# MIC2250-1YD5-TR_breakout.net
KiCad netlist of a schematic drawn in EAGLE
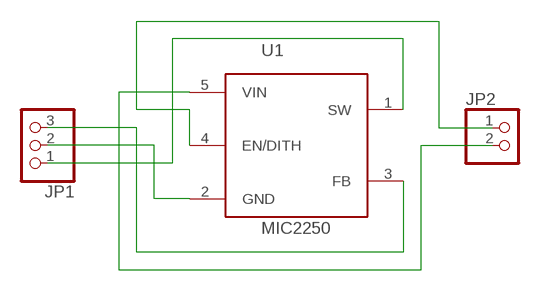
[diagram p0: schematic, sheet 1]

(export (version "E")
  (design (tool "Eeschema 10.0.6"))
  (components
    (comp (ref "JP1")
      (value "PINHD-1X3")
      (footprint "eagle-import:1X03")
      (libsource (lib "eagle-import") (part "PINHD-1X3"))
    )
    (comp (ref "JP2")
      (value "PINHD-1X2")
      (footprint "eagle-import:1X02")
      (libsource (lib "eagle-import") (part "PINHD-1X2"))
    )
    (comp (ref "U1")
      (value "MIC2250")
      (footprint "eagle-import:SOT95P270X145-5N")
      (fields (field (name "MF") "MICROCHIP"))
      (libsource (lib "eagle-import") (part "MIC2250"))
    )
  )
  (nets
    (net (code "1") (name "Net-(U1-EN{slash}DITH)") (class "Default")
      (node (ref "JP2") (pin "1") (pinfunction "1_1") (pintype "passive"))
      (node (ref "U1") (pin "4") (pinfunction "EN/DITH_4") (pintype "bidirectional"))
    )
    (net (code "2") (name "Net-(U1-FB)") (class "Default")
      (node (ref "JP1") (pin "3") (pinfunction "3_3") (pintype "passive"))
      (node (ref "U1") (pin "3") (pinfunction "FB_3") (pintype "bidirectional"))
    )
    (net (code "3") (name "Net-(U1-GND)") (class "Default")
      (node (ref "JP1") (pin "2") (pinfunction "2_2") (pintype "passive"))
      (node (ref "U1") (pin "2") (pinfunction "GND_2") (pintype "power_in"))
    )
    (net (code "4") (name "Net-(U1-SW)") (class "Default")
      (node (ref "JP1") (pin "1") (pinfunction "1_1") (pintype "passive"))
      (node (ref "U1") (pin "1") (pinfunction "SW_1") (pintype "output"))
    )
    (net (code "5") (name "Net-(U1-VIN)") (class "Default")
      (node (ref "JP2") (pin "2") (pinfunction "2_2") (pintype "passive"))
      (node (ref "U1") (pin "5") (pinfunction "VIN_5") (pintype "input"))
    )
  )
)
